# mcu_sys_sch.net
KiCad netlist of a schematic drawn in Altium Designer
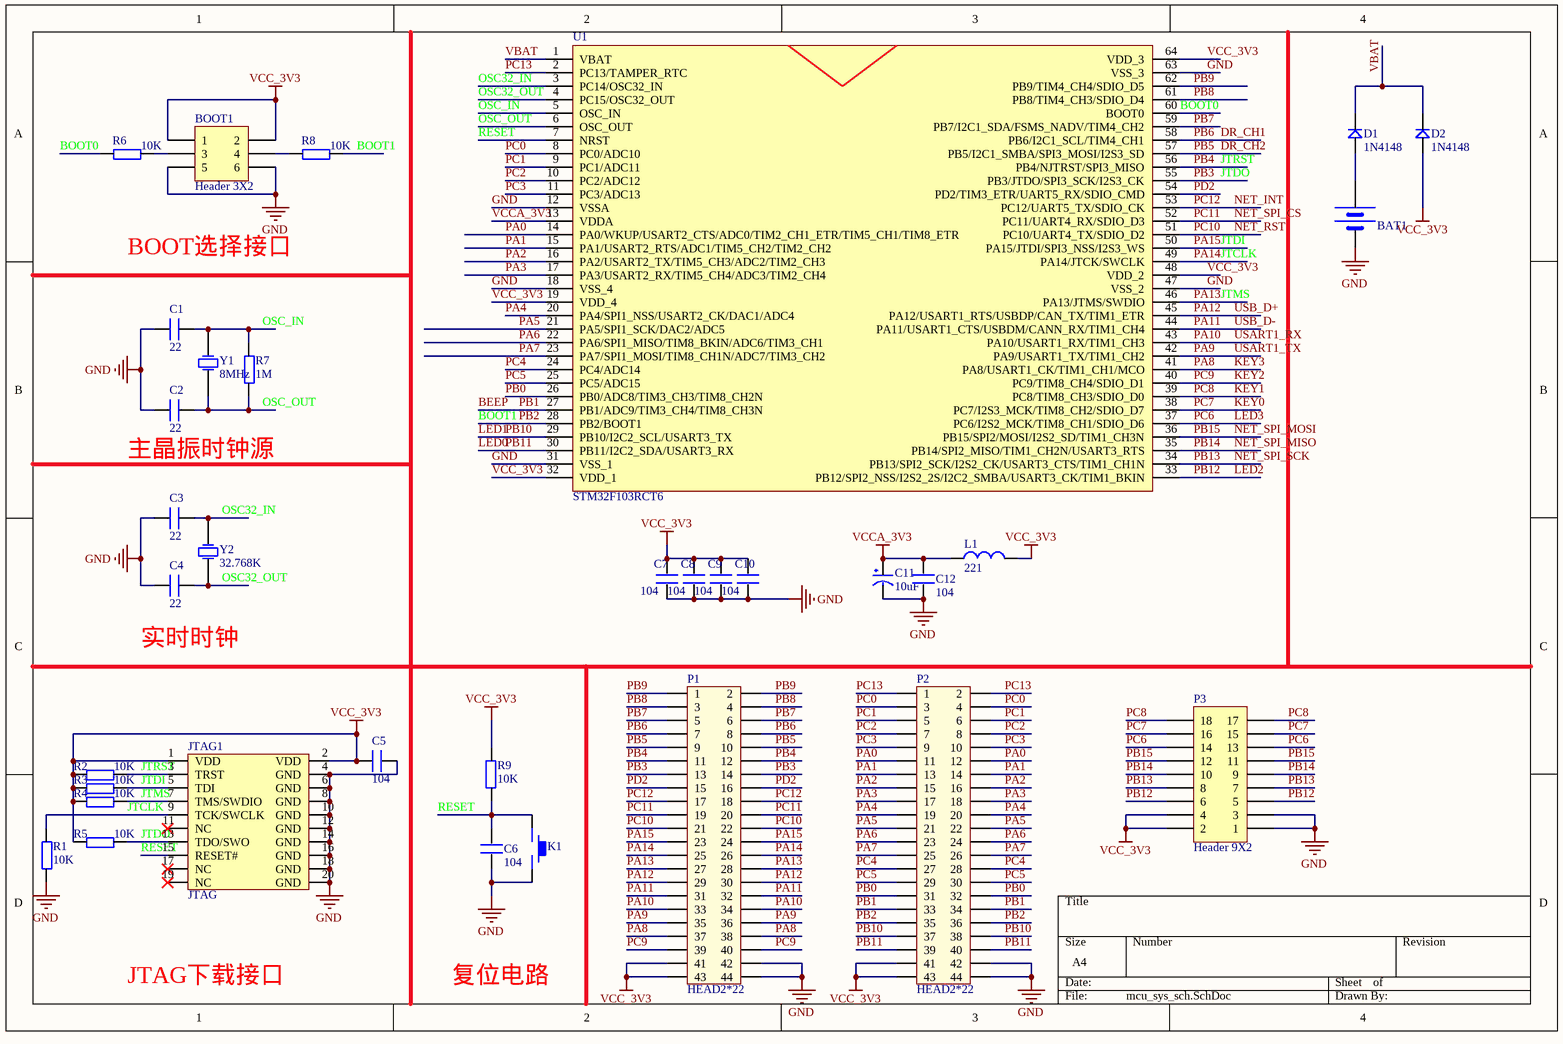
[diagram p0: mcu_sys_sch.SchDoc]

(export (version "E")
  (design (tool "Eeschema 10.0.6"))
  (components
    (comp (ref "BAT1") (value "BATT") (footprint "BATM") (libsource (lib "MY_SCH_Lib") (part "BAT")))
    (comp (ref "BOOT1")
      (value "Header 3X2")
      (footprint "HDR2X3")
      (description "Header, 3-Pin, Dual row")
      (fields (field (name "PUBLISHER") "Altium Limited"))
      (libsource (lib "MY_SCH_Lib") (part "Header 3X2"))
    )
    (comp (ref "C1") (value "22") (footprint "0603P") (libsource (lib "MY_SCH_Lib") (part "C")))
    (comp (ref "C2") (value "22") (footprint "0603P") (libsource (lib "MY_SCH_Lib") (part "C")))
    (comp (ref "C3") (value "22") (footprint "0603P") (libsource (lib "MY_SCH_Lib") (part "C")))
    (comp (ref "C4") (value "22") (footprint "0603P") (libsource (lib "MY_SCH_Lib") (part "C")))
    (comp (ref "C5") (value "104") (footprint "0603P") (libsource (lib "MY_SCH_Lib") (part "C")))
    (comp (ref "C6") (value "104") (footprint "0603P") (libsource (lib "MY_SCH_Lib") (part "C")))
    (comp (ref "C7") (value "104") (footprint "0603P") (libsource (lib "MY_SCH_Lib") (part "C")))
    (comp (ref "C8") (value "104") (footprint "0603P") (libsource (lib "MY_SCH_Lib") (part "C")))
    (comp (ref "C9") (value "104") (footprint "0603P") (libsource (lib "MY_SCH_Lib") (part "C")))
    (comp (ref "C10") (value "104") (footprint "0603P") (libsource (lib "MY_SCH_Lib") (part "C")))
    (comp (ref "C11") (value "10uF") (footprint "TAJ_A") (libsource (lib "MY_SCH_Lib") (part "CAP")))
    (comp (ref "C12") (value "104") (footprint "0603P") (libsource (lib "MY_SCH_Lib") (part "C")))
    (comp (ref "D1") (value "1N4148") (footprint "DIODE_SOP") (libsource (lib "MY_SCH_Lib") (part "D")))
    (comp (ref "D2") (value "1N4148") (footprint "DIODE_SOP") (libsource (lib "MY_SCH_Lib") (part "D")))
    (comp (ref "JTAG1") (value "JTAG") (footprint "JTAG_20") (libsource (lib "MY_SCH_Lib") (part "JTAG")))
    (comp (ref "K1") (value "KEY") (footprint "KEY2") (libsource (lib "MY_SCH_Lib") (part "KEY")))
    (comp (ref "L1") (value "221") (footprint "0603P") (libsource (lib "MY_SCH_Lib") (part "Inductor")))
    (comp (ref "P1")
      (value "HEAD2*22")
      (footprint "HEAD2*22")
      (libsource (lib "MY_SCH_Lib") (part "HEAD2*22"))
    )
    (comp (ref "P2")
      (value "HEAD2*22")
      (footprint "HEAD2*22")
      (libsource (lib "MY_SCH_Lib") (part "HEAD2*22"))
    )
    (comp (ref "P3")
      (value "Header 9X2")
      (footprint "HDR2X9")
      (description "Header, 9-Pin, Dual row")
      (fields (field (name "PUBLISHER") "Altium Limited"))
      (libsource (lib "MY_SCH_Lib") (part "Header 9X2"))
    )
    (comp (ref "R1") (value "10K") (footprint "0603P") (libsource (lib "MY_SCH_Lib") (part "R")))
    (comp (ref "R2") (value "10K") (footprint "0603P") (libsource (lib "MY_SCH_Lib") (part "R")))
    (comp (ref "R3") (value "10K") (footprint "0603P") (libsource (lib "MY_SCH_Lib") (part "R")))
    (comp (ref "R4") (value "10K") (footprint "0603P") (libsource (lib "MY_SCH_Lib") (part "R")))
    (comp (ref "R5") (value "10K") (footprint "0603P") (libsource (lib "MY_SCH_Lib") (part "R")))
    (comp (ref "R6") (value "10K") (footprint "0603P") (libsource (lib "MY_SCH_Lib") (part "R")))
    (comp (ref "R7") (value "1M") (footprint "0603P") (libsource (lib "MY_SCH_Lib") (part "R")))
    (comp (ref "R8") (value "10K") (footprint "0603P") (libsource (lib "MY_SCH_Lib") (part "R")))
    (comp (ref "R9") (value "10K") (footprint "0603P") (libsource (lib "MY_SCH_Lib") (part "R")))
    (comp (ref "U1")
      (value "STM32F103RCT6")
      (footprint "STM-LQFP64_N")
      (libsource (lib "MY_SCH_Lib") (part "STM32F103RCT6"))
    )
    (comp (ref "Y1")
      (value "8MHz")
      (footprint "X-SM49")
      (description "Crystal Oscillator")
      (fields (field (name "PUBLISHER") "Altium Limited"))
      (libsource (lib "MY_SCH_Lib") (part "XTAL"))
    )
    (comp (ref "Y2")
      (value "32.768K")
      (footprint "XTAL32")
      (description "Crystal Oscillator")
      (fields (field (name "PUBLISHER") "Altium Limited"))
      (libsource (lib "MY_SCH_Lib") (part "XTAL"))
    )
  )
  (nets
    (net (code "1") (name "/BEEP") (class "Default")
      (node (ref "P2") (pin "33") (pinfunction "33_33") (pintype "passive"))
      (node (ref "P2") (pin "34") (pinfunction "34_34") (pintype "passive"))
      (node (ref "U1") (pin "27") (pinfunction "PB1/ADC9/TIM3_CH4/TIM8_CH3N_27") (pintype "passive"))
    )
    (net (code "2") (name "/BOOT0") (class "Default")
      (node (ref "R6") (pin "1") (pintype "passive"))
      (node (ref "U1") (pin "60") (pinfunction "BOOT0_60") (pintype "passive"))
    )
    (net (code "3") (name "/BOOT1") (class "Default")
      (node (ref "P2") (pin "35") (pinfunction "35_35") (pintype "passive"))
      (node (ref "P2") (pin "36") (pinfunction "36_36") (pintype "passive"))
      (node (ref "R8") (pin "2") (pintype "passive"))
      (node (ref "U1") (pin "28") (pinfunction "PB2/BOOT1_28") (pintype "passive"))
    )
    (net (code "4") (name "/DR_CH1") (class "Default")
      (node (ref "P1") (pin "7") (pinfunction "7_7") (pintype "passive"))
      (node (ref "P1") (pin "8") (pinfunction "8_8") (pintype "passive"))
      (node (ref "U1") (pin "58") (pinfunction "PB6/I2C1_SCL/TIM4_CH1_58") (pintype "passive"))
    )
    (net (code "5") (name "/DR_CH2") (class "Default")
      (node (ref "P1") (pin "10") (pinfunction "10_10") (pintype "passive"))
      (node (ref "P1") (pin "9") (pinfunction "9_9") (pintype "passive"))
      (node (ref "U1") (pin "57") (pinfunction "PB5/I2C1_SMBA/SPI3_MOSI/I2S3_SD_57") (pintype "passive"))
    )
    (net (code "6") (name "/JTCLK") (class "Default")
      (node (ref "JTAG1") (pin "9") (pinfunction "TCK/SWCLK_9") (pintype "passive"))
      (node (ref "P1") (pin "25") (pinfunction "25_25") (pintype "passive"))
      (node (ref "P1") (pin "26") (pinfunction "26_26") (pintype "passive"))
      (node (ref "R1") (pin "2") (pintype "passive"))
      (node (ref "U1") (pin "49") (pinfunction "PA14/JTCK/SWCLK_49") (pintype "passive"))
    )
    (net (code "7") (name "/JTDI") (class "Default")
      (node (ref "JTAG1") (pin "5") (pinfunction "TDI_5") (pintype "passive"))
      (node (ref "P1") (pin "23") (pinfunction "23_23") (pintype "passive"))
      (node (ref "P1") (pin "24") (pinfunction "24_24") (pintype "passive"))
      (node (ref "R3") (pin "2") (pintype "passive"))
      (node (ref "U1") (pin "50") (pinfunction "PA15/JTDI/SPI3_NSS/I2S3_WS_50") (pintype "passive"))
    )
    (net (code "8") (name "/JTDO") (class "Default")
      (node (ref "JTAG1") (pin "13") (pinfunction "TDO/SWO_13") (pintype "passive"))
      (node (ref "P1") (pin "13") (pinfunction "13_13") (pintype "passive"))
      (node (ref "P1") (pin "14") (pinfunction "14_14") (pintype "passive"))
      (node (ref "R5") (pin "2") (pintype "passive"))
      (node (ref "U1") (pin "55") (pinfunction "PB3/JTDO/SPI3_SCK/I2S3_CK_55") (pintype "passive"))
    )
    (net (code "9") (name "/JTMS") (class "Default")
      (node (ref "JTAG1") (pin "7") (pinfunction "TMS/SWDIO_7") (pintype "passive"))
      (node (ref "P1") (pin "27") (pinfunction "27_27") (pintype "passive"))
      (node (ref "P1") (pin "28") (pinfunction "28_28") (pintype "passive"))
      (node (ref "R4") (pin "2") (pintype "passive"))
      (node (ref "U1") (pin "46") (pinfunction "PA13/JTMS/SWDIO_46") (pintype "passive"))
    )
    (net (code "10") (name "/JTRST") (class "Default")
      (node (ref "JTAG1") (pin "3") (pinfunction "TRST_3") (pintype "passive"))
      (node (ref "P1") (pin "11") (pinfunction "11_11") (pintype "passive"))
      (node (ref "P1") (pin "12") (pinfunction "12_12") (pintype "passive"))
      (node (ref "R2") (pin "2") (pintype "passive"))
      (node (ref "U1") (pin "56") (pinfunction "PB4/NJTRST/SPI3_MISO_56") (pintype "passive"))
    )
    (net (code "11") (name "/KEY0") (class "Default")
      (node (ref "P3") (pin "15") (pinfunction "15_15") (pintype "passive"))
      (node (ref "P3") (pin "16") (pinfunction "16_16") (pintype "passive"))
      (node (ref "U1") (pin "38") (pinfunction "PC7/I2S3_MCK/TIM8_CH2/SDIO_D7_38") (pintype "passive"))
    )
    (net (code "12") (name "/KEY1") (class "Default")
      (node (ref "P3") (pin "17") (pinfunction "17_17") (pintype "passive"))
      (node (ref "P3") (pin "18") (pinfunction "18_18") (pintype "passive"))
      (node (ref "U1") (pin "39") (pinfunction "PC8/TIM8_CH3/SDIO_D0_39") (pintype "passive"))
    )
    (net (code "13") (name "/KEY2") (class "Default")
      (node (ref "P1") (pin "39") (pinfunction "39_39") (pintype "passive"))
      (node (ref "P1") (pin "40") (pinfunction "40_40") (pintype "passive"))
      (node (ref "U1") (pin "40") (pinfunction "PC9/TIM8_CH4/SDIO_D1_40") (pintype "passive"))
    )
    (net (code "14") (name "/KEY3") (class "Default")
      (node (ref "P1") (pin "37") (pinfunction "37_37") (pintype "passive"))
      (node (ref "P1") (pin "38") (pinfunction "38_38") (pintype "passive"))
      (node (ref "U1") (pin "41") (pinfunction "PA8/USART1_CK/TIM1_CH1/MCO_41") (pintype "passive"))
    )
    (net (code "15") (name "/LED0") (class "Default")
      (node (ref "P2") (pin "39") (pinfunction "39_39") (pintype "passive"))
      (node (ref "P2") (pin "40") (pinfunction "40_40") (pintype "passive"))
      (node (ref "U1") (pin "30") (pinfunction "PB11/I2C2_SDA/USART3_RX_30") (pintype "passive"))
    )
    (net (code "16") (name "/LED1") (class "Default")
      (node (ref "P2") (pin "37") (pinfunction "37_37") (pintype "passive"))
      (node (ref "P2") (pin "38") (pinfunction "38_38") (pintype "passive"))
      (node (ref "U1") (pin "29") (pinfunction "PB10/I2C2_SCL/USART3_TX_29") (pintype "passive"))
    )
    (net (code "17") (name "/LED2") (class "Default")
      (node (ref "P3") (pin "5") (pinfunction "5_5") (pintype "passive"))
      (node (ref "P3") (pin "6") (pinfunction "6_6") (pintype "passive"))
      (node (ref "U1") (pin "33") (pinfunction "PB12/SPI2_NSS/I2S2_2S/I2C2_SMBA/USART3_CK/TIM1_BKIN_33") (pintype "passive"))
    )
    (net (code "18") (name "/LED3") (class "Default")
      (node (ref "P3") (pin "13") (pinfunction "13_13") (pintype "passive"))
      (node (ref "P3") (pin "14") (pinfunction "14_14") (pintype "passive"))
      (node (ref "U1") (pin "37") (pinfunction "PC6/I2S2_MCK/TIM8_CH1/SDIO_D6_37") (pintype "passive"))
    )
    (net (code "19") (name "/NET_INT") (class "Default")
      (node (ref "P1") (pin "17") (pinfunction "17_17") (pintype "passive"))
      (node (ref "P1") (pin "18") (pinfunction "18_18") (pintype "passive"))
      (node (ref "U1") (pin "53") (pinfunction "PC12/UART5_TX/SDIO_CK_53") (pintype "passive"))
    )
    (net (code "20") (name "/NET_RST") (class "Default")
      (node (ref "P1") (pin "21") (pinfunction "21_21") (pintype "passive"))
      (node (ref "P1") (pin "22") (pinfunction "22_22") (pintype "passive"))
      (node (ref "U1") (pin "51") (pinfunction "PC10/UART4_TX/SDIO_D2_51") (pintype "passive"))
    )
    (net (code "21") (name "/NET_SPI_CS") (class "Default")
      (node (ref "P1") (pin "19") (pinfunction "19_19") (pintype "passive"))
      (node (ref "P1") (pin "20") (pinfunction "20_20") (pintype "passive"))
      (node (ref "U1") (pin "52") (pinfunction "PC11/UART4_RX/SDIO_D3_52") (pintype "passive"))
    )
    (net (code "22") (name "/NET_SPI_MISO") (class "Default")
      (node (ref "P3") (pin "10") (pinfunction "10_10") (pintype "passive"))
      (node (ref "P3") (pin "9") (pinfunction "9_9") (pintype "passive"))
      (node (ref "U1") (pin "35") (pinfunction "PB14/SPI2_MISO/TIM1_CH2N/USART3_RTS_35") (pintype "passive"))
    )
    (net (code "23") (name "/NET_SPI_MOSI") (class "Default")
      (node (ref "P3") (pin "11") (pinfunction "11_11") (pintype "passive"))
      (node (ref "P3") (pin "12") (pinfunction "12_12") (pintype "passive"))
      (node (ref "U1") (pin "36") (pinfunction "PB15/SPI2/MOSI/I2S2_SD/TIM1_CH3N_36") (pintype "passive"))
    )
    (net (code "24") (name "/NET_SPI_SCK") (class "Default")
      (node (ref "P3") (pin "7") (pinfunction "7_7") (pintype "passive"))
      (node (ref "P3") (pin "8") (pinfunction "8_8") (pintype "passive"))
      (node (ref "U1") (pin "34") (pinfunction "PB13/SPI2_SCK/I2S2_CK/USART3_CTS/TIM1_CH1N_34") (pintype "passive"))
    )
    (net (code "25") (name "/OSC32_IN") (class "Default")
      (node (ref "C3") (pin "2") (pintype "passive"))
      (node (ref "U1") (pin "3") (pinfunction "PC14/OSC32_IN_3") (pintype "passive"))
      (node (ref "Y2") (pin "2") (pinfunction "OSC2_2") (pintype "passive"))
    )
    (net (code "26") (name "/OSC32_OUT") (class "Default")
      (node (ref "C4") (pin "2") (pintype "passive"))
      (node (ref "U1") (pin "4") (pinfunction "PC15/OSC32_OUT_4") (pintype "passive"))
      (node (ref "Y2") (pin "1") (pinfunction "OSC1_1") (pintype "passive"))
    )
    (net (code "27") (name "/OSC_IN") (class "Default")
      (node (ref "C1") (pin "2") (pintype "passive"))
      (node (ref "R7") (pin "2") (pintype "passive"))
      (node (ref "U1") (pin "5") (pinfunction "OSC_IN_5") (pintype "passive"))
      (node (ref "Y1") (pin "2") (pinfunction "OSC2_2") (pintype "passive"))
    )
    (net (code "28") (name "/OSC_OUT") (class "Default")
      (node (ref "C2") (pin "2") (pintype "passive"))
      (node (ref "R7") (pin "1") (pintype "passive"))
      (node (ref "U1") (pin "6") (pinfunction "OSC_OUT_6") (pintype "passive"))
      (node (ref "Y1") (pin "1") (pinfunction "OSC1_1") (pintype "passive"))
    )
    (net (code "29") (name "/PA0") (class "Default")
      (node (ref "P2") (pin "11") (pinfunction "11_11") (pintype "passive"))
      (node (ref "P2") (pin "12") (pinfunction "12_12") (pintype "passive"))
      (node (ref "U1") (pin "14") (pinfunction "PA0/WKUP/USART2_CTS/ADC0/TIM2_CH1_ETR/TIM5_CH1/TIM8_ETR_14") (pintype "passive"))
    )
    (net (code "30") (name "/PA1") (class "Default")
      (node (ref "P2") (pin "13") (pinfunction "13_13") (pintype "passive"))
      (node (ref "P2") (pin "14") (pinfunction "14_14") (pintype "passive"))
      (node (ref "U1") (pin "15") (pinfunction "PA1/USART2_RTS/ADC1/TIM5_CH2/TIM2_CH2_15") (pintype "passive"))
    )
    (net (code "31") (name "/PA2") (class "Default")
      (node (ref "P2") (pin "15") (pinfunction "15_15") (pintype "passive"))
      (node (ref "P2") (pin "16") (pinfunction "16_16") (pintype "passive"))
      (node (ref "U1") (pin "16") (pinfunction "PA2/USART2_TX/TIM5_CH3/ADC2/TIM2_CH3_16") (pintype "passive"))
    )
    (net (code "32") (name "/PA3") (class "Default")
      (node (ref "P2") (pin "17") (pinfunction "17_17") (pintype "passive"))
      (node (ref "P2") (pin "18") (pinfunction "18_18") (pintype "passive"))
      (node (ref "U1") (pin "17") (pinfunction "PA3/USART2_RX/TIM5_CH4/ADC3/TIM2_CH4_17") (pintype "passive"))
    )
    (net (code "33") (name "/PA4") (class "Default")
      (node (ref "P2") (pin "19") (pinfunction "19_19") (pintype "passive"))
      (node (ref "P2") (pin "20") (pinfunction "20_20") (pintype "passive"))
      (node (ref "U1") (pin "20") (pinfunction "PA4/SPI1_NSS/USART2_CK/DAC1/ADC4_20") (pintype "passive"))
    )
    (net (code "34") (name "/PA5") (class "Default")
      (node (ref "P2") (pin "21") (pinfunction "21_21") (pintype "passive"))
      (node (ref "P2") (pin "22") (pinfunction "22_22") (pintype "passive"))
      (node (ref "U1") (pin "21") (pinfunction "PA5/SPI1_SCK/DAC2/ADC5_21") (pintype "passive"))
    )
    (net (code "35") (name "/PA6") (class "Default")
      (node (ref "P2") (pin "23") (pinfunction "23_23") (pintype "passive"))
      (node (ref "P2") (pin "24") (pinfunction "24_24") (pintype "passive"))
      (node (ref "U1") (pin "22") (pinfunction "PA6/SPI1_MISO/TIM8_BKIN/ADC6/TIM3_CH1_22") (pintype "passive"))
    )
    (net (code "36") (name "/PA7") (class "Default")
      (node (ref "P2") (pin "25") (pinfunction "25_25") (pintype "passive"))
      (node (ref "P2") (pin "26") (pinfunction "26_26") (pintype "passive"))
      (node (ref "U1") (pin "23") (pinfunction "PA7/SPI1_MOSI/TIM8_CH1N/ADC7/TIM3_CH2_23") (pintype "passive"))
    )
    (net (code "37") (name "/PA9") (class "Default")
      (node (ref "P1") (pin "35") (pinfunction "35_35") (pintype "passive"))
      (node (ref "P1") (pin "36") (pinfunction "36_36") (pintype "passive"))
      (node (ref "U1") (pin "42") (pinfunction "PA9/USART1_TX/TIM1_CH2_42") (pintype "passive"))
    )
    (net (code "38") (name "/PA10") (class "Default")
      (node (ref "P1") (pin "33") (pinfunction "33_33") (pintype "passive"))
      (node (ref "P1") (pin "34") (pinfunction "34_34") (pintype "passive"))
      (node (ref "U1") (pin "43") (pinfunction "PA10/USART1_RX/TIM1_CH3_43") (pintype "passive"))
    )
    (net (code "39") (name "/PA11") (class "Default")
      (node (ref "P1") (pin "31") (pinfunction "31_31") (pintype "passive"))
      (node (ref "P1") (pin "32") (pinfunction "32_32") (pintype "passive"))
      (node (ref "U1") (pin "44") (pinfunction "PA11/USART1_CTS/USBDM/CANN_RX/TIM1_CH4_44") (pintype "passive"))
    )
    (net (code "40") (name "/PA12") (class "Default")
      (node (ref "P1") (pin "29") (pinfunction "29_29") (pintype "passive"))
      (node (ref "P1") (pin "30") (pinfunction "30_30") (pintype "passive"))
      (node (ref "U1") (pin "45") (pinfunction "PA12/USART1_RTS/USBDP/CAN_TX/TIM1_ETR_45") (pintype "passive"))
    )
    (net (code "41") (name "/PB0") (class "Default")
      (node (ref "P2") (pin "31") (pinfunction "31_31") (pintype "passive"))
      (node (ref "P2") (pin "32") (pinfunction "32_32") (pintype "passive"))
      (node (ref "U1") (pin "26") (pinfunction "PB0/ADC8/TIM3_CH3/TIM8_CH2N_26") (pintype "passive"))
    )
    (net (code "42") (name "/PB7") (class "Default")
      (node (ref "P1") (pin "5") (pinfunction "5_5") (pintype "passive"))
      (node (ref "P1") (pin "6") (pinfunction "6_6") (pintype "passive"))
      (node (ref "U1") (pin "59") (pinfunction "PB7/I2C1_SDA/FSMS_NADV/TIM4_CH2_59") (pintype "passive"))
    )
    (net (code "43") (name "/PB8") (class "Default")
      (node (ref "P1") (pin "3") (pinfunction "3_3") (pintype "passive"))
      (node (ref "P1") (pin "4") (pinfunction "4_4") (pintype "passive"))
      (node (ref "U1") (pin "61") (pinfunction "PB8/TIM4_CH3/SDIO_D4_61") (pintype "passive"))
    )
    (net (code "44") (name "/PB9") (class "Default")
      (node (ref "P1") (pin "1") (pinfunction "1_1") (pintype "passive"))
      (node (ref "P1") (pin "2") (pinfunction "2_2") (pintype "passive"))
      (node (ref "U1") (pin "62") (pinfunction "PB9/TIM4_CH4/SDIO_D5_62") (pintype "passive"))
    )
    (net (code "45") (name "/PC0") (class "Default")
      (node (ref "P2") (pin "3") (pinfunction "3_3") (pintype "passive"))
      (node (ref "P2") (pin "4") (pinfunction "4_4") (pintype "passive"))
      (node (ref "U1") (pin "8") (pinfunction "PC0/ADC10_8") (pintype "passive"))
    )
    (net (code "46") (name "/PC1") (class "Default")
      (node (ref "P2") (pin "5") (pinfunction "5_5") (pintype "passive"))
      (node (ref "P2") (pin "6") (pinfunction "6_6") (pintype "passive"))
      (node (ref "U1") (pin "9") (pinfunction "PC1/ADC11_9") (pintype "passive"))
    )
    (net (code "47") (name "/PC2") (class "Default")
      (node (ref "P2") (pin "7") (pinfunction "7_7") (pintype "passive"))
      (node (ref "P2") (pin "8") (pinfunction "8_8") (pintype "passive"))
      (node (ref "U1") (pin "10") (pinfunction "PC2/ADC12_10") (pintype "passive"))
    )
    (net (code "48") (name "/PC3") (class "Default")
      (node (ref "P2") (pin "10") (pinfunction "10_10") (pintype "passive"))
      (node (ref "P2") (pin "9") (pinfunction "9_9") (pintype "passive"))
      (node (ref "U1") (pin "11") (pinfunction "PC3/ADC13_11") (pintype "passive"))
    )
    (net (code "49") (name "/PC4") (class "Default")
      (node (ref "P2") (pin "27") (pinfunction "27_27") (pintype "passive"))
      (node (ref "P2") (pin "28") (pinfunction "28_28") (pintype "passive"))
      (node (ref "U1") (pin "24") (pinfunction "PC4/ADC14_24") (pintype "passive"))
    )
    (net (code "50") (name "/PC5") (class "Default")
      (node (ref "P2") (pin "29") (pinfunction "29_29") (pintype "passive"))
      (node (ref "P2") (pin "30") (pinfunction "30_30") (pintype "passive"))
      (node (ref "U1") (pin "25") (pinfunction "PC5/ADC15_25") (pintype "passive"))
    )
    (net (code "51") (name "/PC13") (class "Default")
      (node (ref "P2") (pin "1") (pinfunction "1_1") (pintype "passive"))
      (node (ref "P2") (pin "2") (pinfunction "2_2") (pintype "passive"))
      (node (ref "U1") (pin "2") (pinfunction "PC13/TAMPER_RTC_2") (pintype "passive"))
    )
    (net (code "52") (name "/PD2") (class "Default")
      (node (ref "P1") (pin "15") (pinfunction "15_15") (pintype "passive"))
      (node (ref "P1") (pin "16") (pinfunction "16_16") (pintype "passive"))
      (node (ref "U1") (pin "54") (pinfunction "PD2/TIM3_ETR/UART5_RX/SDIO_CMD_54") (pintype "passive"))
    )
    (net (code "53") (name "/RESET") (class "Default")
      (node (ref "C6") (pin "2") (pintype "passive"))
      (node (ref "JTAG1") (pin "15") (pinfunction "RESET#_15") (pintype "passive"))
      (node (ref "K1") (pin "2") (pinfunction "2_2") (pintype "passive"))
      (node (ref "R9") (pin "1") (pintype "passive"))
      (node (ref "U1") (pin "7") (pinfunction "NRST_7") (pintype "passive"))
    )
    (net (code "54") (name "/VBAT") (class "Default")
      (node (ref "D1") (pin "2") (pintype "passive"))
      (node (ref "D2") (pin "2") (pintype "passive"))
      (node (ref "U1") (pin "1") (pinfunction "VBAT_1") (pintype "passive"))
    )
    (net (code "55") (name "GND") (class "Default")
      (node (ref "BAT1") (pin "2") (pinfunction "GND_2") (pintype "passive"))
      (node (ref "BOOT1") (pin "5") (pinfunction "5_5") (pintype "passive"))
      (node (ref "BOOT1") (pin "6") (pinfunction "6_6") (pintype "passive"))
      (node (ref "C1") (pin "1") (pintype "passive"))
      (node (ref "C10") (pin "1") (pintype "passive"))
      (node (ref "C11") (pin "2") (pinfunction "GND_2") (pintype "passive"))
      (node (ref "C12") (pin "1") (pintype "passive"))
      (node (ref "C2") (pin "1") (pintype "passive"))
      (node (ref "C3") (pin "1") (pintype "passive"))
      (node (ref "C4") (pin "1") (pintype "passive"))
      (node (ref "C5") (pin "2") (pintype "passive"))
      (node (ref "C6") (pin "1") (pintype "passive"))
      (node (ref "C7") (pin "1") (pintype "passive"))
      (node (ref "C8") (pin "1") (pintype "passive"))
      (node (ref "C9") (pin "1") (pintype "passive"))
      (node (ref "JTAG1") (pin "10") (pinfunction "GND_10") (pintype "passive"))
      (node (ref "JTAG1") (pin "12") (pinfunction "GND_12") (pintype "passive"))
      (node (ref "JTAG1") (pin "14") (pinfunction "GND_14") (pintype "passive"))
      (node (ref "JTAG1") (pin "16") (pinfunction "GND_16") (pintype "passive"))
      (node (ref "JTAG1") (pin "18") (pinfunction "GND_18") (pintype "passive"))
      (node (ref "JTAG1") (pin "20") (pinfunction "GND_20") (pintype "passive"))
      (node (ref "JTAG1") (pin "4") (pinfunction "GND_4") (pintype "passive"))
      (node (ref "JTAG1") (pin "6") (pinfunction "GND_6") (pintype "passive"))
      (node (ref "JTAG1") (pin "8") (pinfunction "GND_8") (pintype "passive"))
      (node (ref "K1") (pin "1") (pinfunction "1_1") (pintype "passive"))
      (node (ref "P1") (pin "42") (pinfunction "42_42") (pintype "passive"))
      (node (ref "P1") (pin "44") (pinfunction "44_44") (pintype "passive"))
      (node (ref "P2") (pin "42") (pinfunction "42_42") (pintype "passive"))
      (node (ref "P2") (pin "44") (pinfunction "44_44") (pintype "passive"))
      (node (ref "P3") (pin "1") (pinfunction "1_1") (pintype "passive"))
      (node (ref "P3") (pin "3") (pinfunction "3_3") (pintype "passive"))
      (node (ref "R1") (pin "1") (pintype "passive"))
      (node (ref "U1") (pin "12") (pinfunction "VSSA_12") (pintype "passive"))
      (node (ref "U1") (pin "18") (pinfunction "VSS_4_18") (pintype "passive"))
      (node (ref "U1") (pin "31") (pinfunction "VSS_1_31") (pintype "passive"))
      (node (ref "U1") (pin "47") (pinfunction "VSS_2_47") (pintype "passive"))
      (node (ref "U1") (pin "63") (pinfunction "VSS_3_63") (pintype "passive"))
    )
    (net (code "56") (name "Net-(BAT1-VCC)") (class "Default")
      (node (ref "BAT1") (pin "1") (pinfunction "VCC_1") (pintype "passive"))
      (node (ref "D1") (pin "1") (pintype "passive"))
    )
    (net (code "57") (name "Net-(BOOT1-Pad3)") (class "Default")
      (node (ref "BOOT1") (pin "3") (pinfunction "3_3") (pintype "passive"))
      (node (ref "R6") (pin "2") (pintype "passive"))
    )
    (net (code "58") (name "Net-(BOOT1-Pad4)") (class "Default")
      (node (ref "BOOT1") (pin "4") (pinfunction "4_4") (pintype "passive"))
      (node (ref "R8") (pin "1") (pintype "passive"))
    )
    (net (code "59") (name "VCCA_3V3") (class "Default")
      (node (ref "C11") (pin "1") (pinfunction "VCC_1") (pintype "passive"))
      (node (ref "C12") (pin "2") (pintype "passive"))
      (node (ref "L1") (pin "1") (pinfunction "1_1") (pintype "passive"))
      (node (ref "U1") (pin "13") (pinfunction "VDDA_13") (pintype "passive"))
    )
    (net (code "60") (name "VCC_3V3") (class "Default")
      (node (ref "BOOT1") (pin "1") (pinfunction "1_1") (pintype "passive"))
      (node (ref "BOOT1") (pin "2") (pinfunction "2_2") (pintype "passive"))
      (node (ref "C10") (pin "2") (pintype "passive"))
      (node (ref "C5") (pin "1") (pintype "passive"))
      (node (ref "C7") (pin "2") (pintype "passive"))
      (node (ref "C8") (pin "2") (pintype "passive"))
      (node (ref "C9") (pin "2") (pintype "passive"))
      (node (ref "D2") (pin "1") (pintype "passive"))
      (node (ref "JTAG1") (pin "1") (pinfunction "VDD_1") (pintype "passive"))
      (node (ref "JTAG1") (pin "2") (pinfunction "VDD_2") (pintype "passive"))
      (node (ref "L1") (pin "2") (pinfunction "2_2") (pintype "passive"))
      (node (ref "P1") (pin "41") (pinfunction "41_41") (pintype "passive"))
      (node (ref "P1") (pin "43") (pinfunction "43_43") (pintype "passive"))
      (node (ref "P2") (pin "41") (pinfunction "41_41") (pintype "passive"))
      (node (ref "P2") (pin "43") (pinfunction "43_43") (pintype "passive"))
      (node (ref "P3") (pin "2") (pinfunction "2_2") (pintype "passive"))
      (node (ref "P3") (pin "4") (pinfunction "4_4") (pintype "passive"))
      (node (ref "R2") (pin "1") (pintype "passive"))
      (node (ref "R3") (pin "1") (pintype "passive"))
      (node (ref "R4") (pin "1") (pintype "passive"))
      (node (ref "R5") (pin "1") (pintype "passive"))
      (node (ref "R9") (pin "2") (pintype "passive"))
      (node (ref "U1") (pin "19") (pinfunction "VDD_4_19") (pintype "passive"))
      (node (ref "U1") (pin "32") (pinfunction "VDD_1_32") (pintype "passive"))
      (node (ref "U1") (pin "48") (pinfunction "VDD_2_48") (pintype "passive"))
      (node (ref "U1") (pin "64") (pinfunction "VDD_3_64") (pintype "passive"))
    )
    (net (code "61") (name "unconnected-(JTAG1-NC-Pad11)") (class "Default")
      (node (ref "JTAG1") (pin "11") (pinfunction "NC_11") (pintype "passive+no_connect"))
    )
    (net (code "62") (name "unconnected-(JTAG1-NC-Pad17)") (class "Default")
      (node (ref "JTAG1") (pin "17") (pinfunction "NC_17") (pintype "passive+no_connect"))
    )
    (net (code "63") (name "unconnected-(JTAG1-NC-Pad19)") (class "Default")
      (node (ref "JTAG1") (pin "19") (pinfunction "NC_19") (pintype "passive+no_connect"))
    )
  )
)
